# Inverter.net
KiCad netlist of a schematic drawn in Altium Designer
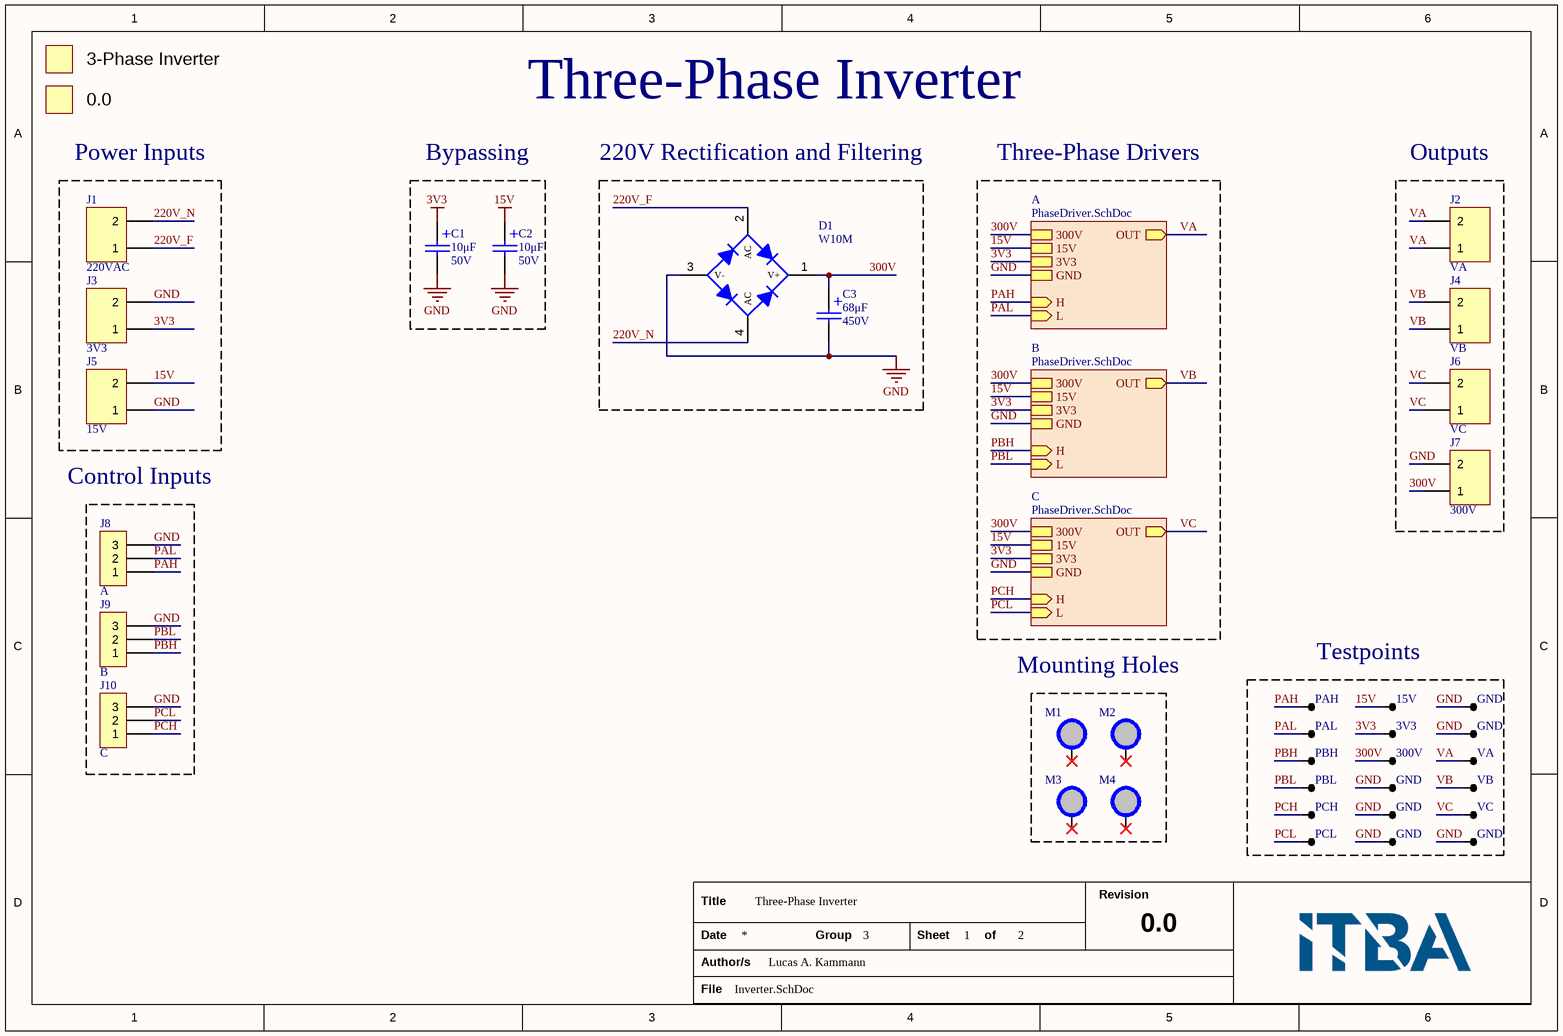
[diagram p0: Inverter.SchDoc]

(export (version "E")
  (design (tool "Eeschema 10.0.6"))
  (components
    (comp (ref "B1")
      (value "Board Name")
      (footprint "MISC_BOARD")
      (fields (field (name "NAME") "3-Phase Inverter"))
      (libsource (lib "Inverter") (part "MISC_BOARD"))
    )
    (comp (ref "C1")
      (value "10μF")
      (footprint "CAP100RP")
      (description "CAPACITOR POLARIZADO")
      (fields (field (name "VOLTAGE RATING") "50V") (field (name "Comment") "CAPPOL"))
      (libsource (lib "Inverter") (part "CAPACITOR POLARIZADO"))
    )
    (comp (ref "C2")
      (value "10μF")
      (footprint "CAP100RP")
      (description "CAPACITOR POLARIZADO")
      (fields (field (name "VOLTAGE RATING") "50V") (field (name "Comment") "CAPPOL"))
      (libsource (lib "Inverter") (part "CAPACITOR POLARIZADO"))
    )
    (comp (ref "C3")
      (value "68μF")
      (footprint "CAP_8mm")
      (description "CAPACITOR POLARIZADO")
      (fields (field (name "VOLTAGE RATING") "450V") (field (name "Comment") "CAPPOL"))
      (libsource (lib "Inverter") (part "CAPACITOR POLARIZADO"))
    )
    (comp (ref "D1") (value "W10M") (footprint "PUENTE - W10M") (libsource (lib "Inverter") (part "W10M")))
    (comp (ref "J1")
      (value "220VAC")
      (footprint "BORNERA2")
      (description "BORNERA 2 POLOS")
      (libsource (lib "Inverter") (part "BORNERA 2"))
    )
    (comp (ref "J2")
      (value "VA")
      (footprint "BORNERA2")
      (description "BORNERA 2 POLOS")
      (libsource (lib "") (part "BORNERA 2_1"))
    )
    (comp (ref "J3")
      (value "3V3")
      (footprint "BORNERA2")
      (description "BORNERA 2 POLOS")
      (libsource (lib "Inverter") (part "BORNERA 2"))
    )
    (comp (ref "J4")
      (value "VB")
      (footprint "BORNERA2")
      (description "BORNERA 2 POLOS")
      (libsource (lib "") (part "BORNERA 2_1"))
    )
    (comp (ref "J5")
      (value "15V")
      (footprint "BORNERA2")
      (description "BORNERA 2 POLOS")
      (libsource (lib "Inverter") (part "BORNERA 2"))
    )
    (comp (ref "J6")
      (value "VC")
      (footprint "BORNERA2")
      (description "BORNERA 2 POLOS")
      (libsource (lib "") (part "BORNERA 2_1"))
    )
    (comp (ref "J7")
      (value "300V")
      (footprint "BORNERA2")
      (description "BORNERA 2 POLOS")
      (libsource (lib "") (part "BORNERA 2_1"))
    )
    (comp (ref "J8") (value "A") (footprint "SIP3") (libsource (lib "*") (part "CON3")))
    (comp (ref "J9") (value "B") (footprint "SIP3") (libsource (lib "*") (part "CON3")))
    (comp (ref "J10") (value "C") (footprint "SIP3") (libsource (lib "*") (part "CON3")))
    (comp (ref "M1")
      (value "Mounting Hole")
      (footprint "MISC_MOUNTING_HOLE_M3")
      (description "MOUNTING HOLE M2.5")
      (libsource (lib "Inverter") (part "MISC_MOUNTING_HOLE_M3"))
    )
    (comp (ref "M2")
      (value "Mounting Hole")
      (footprint "MISC_MOUNTING_HOLE_M3")
      (description "MOUNTING HOLE M2.5")
      (libsource (lib "Inverter") (part "MISC_MOUNTING_HOLE_M3"))
    )
    (comp (ref "M3")
      (value "Mounting Hole")
      (footprint "MISC_MOUNTING_HOLE_M3")
      (description "MOUNTING HOLE M2.5")
      (libsource (lib "Inverter") (part "MISC_MOUNTING_HOLE_M3"))
    )
    (comp (ref "M4")
      (value "Mounting Hole")
      (footprint "MISC_MOUNTING_HOLE_M3")
      (description "MOUNTING HOLE M2.5")
      (libsource (lib "Inverter") (part "MISC_MOUNTING_HOLE_M3"))
    )
    (comp (ref "TP1")
      (value "PAH")
      (footprint "TPTH")
      (description "TESTPOINT")
      (libsource (lib "Inverter") (part "TP"))
    )
    (comp (ref "TP2")
      (value "15V")
      (footprint "TPTH")
      (description "TESTPOINT")
      (libsource (lib "Inverter") (part "TP"))
    )
    (comp (ref "TP3")
      (value "GND")
      (footprint "TPTH")
      (description "TESTPOINT")
      (libsource (lib "Inverter") (part "TP"))
    )
    (comp (ref "TP4")
      (value "PAL")
      (footprint "TPTH")
      (description "TESTPOINT")
      (libsource (lib "Inverter") (part "TP"))
    )
    (comp (ref "TP5")
      (value "3V3")
      (footprint "TPTH")
      (description "TESTPOINT")
      (libsource (lib "Inverter") (part "TP"))
    )
    (comp (ref "TP6")
      (value "GND")
      (footprint "TPTH")
      (description "TESTPOINT")
      (libsource (lib "Inverter") (part "TP"))
    )
    (comp (ref "TP7")
      (value "PBH")
      (footprint "TPTH")
      (description "TESTPOINT")
      (libsource (lib "Inverter") (part "TP"))
    )
    (comp (ref "TP8")
      (value "300V")
      (footprint "TPTH")
      (description "TESTPOINT")
      (libsource (lib "Inverter") (part "TP"))
    )
    (comp (ref "TP9")
      (value "VA")
      (footprint "TPTH")
      (description "TESTPOINT")
      (libsource (lib "Inverter") (part "TP"))
    )
    (comp (ref "TP10")
      (value "PBL")
      (footprint "TPTH")
      (description "TESTPOINT")
      (libsource (lib "Inverter") (part "TP"))
    )
    (comp (ref "TP11")
      (value "GND")
      (footprint "TPTH")
      (description "TESTPOINT")
      (libsource (lib "Inverter") (part "TP"))
    )
    (comp (ref "TP12")
      (value "VB")
      (footprint "TPTH")
      (description "TESTPOINT")
      (libsource (lib "Inverter") (part "TP"))
    )
    (comp (ref "TP13")
      (value "PCH")
      (footprint "TPTH")
      (description "TESTPOINT")
      (libsource (lib "Inverter") (part "TP"))
    )
    (comp (ref "TP14")
      (value "GND")
      (footprint "TPTH")
      (description "TESTPOINT")
      (libsource (lib "Inverter") (part "TP"))
    )
    (comp (ref "TP15")
      (value "VC")
      (footprint "TPTH")
      (description "TESTPOINT")
      (libsource (lib "Inverter") (part "TP"))
    )
    (comp (ref "TP16")
      (value "PCL")
      (footprint "TPTH")
      (description "TESTPOINT")
      (libsource (lib "Inverter") (part "TP"))
    )
    (comp (ref "TP17")
      (value "GND")
      (footprint "TPTH")
      (description "TESTPOINT")
      (libsource (lib "Inverter") (part "TP"))
    )
    (comp (ref "TP18")
      (value "GND")
      (footprint "TPTH")
      (description "TESTPOINT")
      (libsource (lib "Inverter") (part "TP"))
    )
    (comp (ref "V1")
      (value "PCB Version")
      (footprint "MISC_VERSION")
      (fields (field (name "VERSION") "0.0"))
      (libsource (lib "Inverter") (part "MISC_VERSION"))
    )
  )
  (nets
    (net (code "1") (name "/220V_F") (class "Default")
      (node (ref "D1") (pin "2") (pinfunction "AC_2") (pintype "passive"))
      (node (ref "J1") (pin "1") (pinfunction "1_1") (pintype "passive"))
    )
    (net (code "2") (name "/220V_N") (class "Default")
      (node (ref "D1") (pin "4") (pinfunction "AC_4") (pintype "passive"))
      (node (ref "J1") (pin "2") (pinfunction "2_2") (pintype "passive"))
    )
    (net (code "3") (name "/300V") (class "Default")
      (node (ref "C3") (pin "1") (pinfunction "1_1") (pintype "passive"))
      (node (ref "D1") (pin "1") (pinfunction "V+_1") (pintype "passive"))
      (node (ref "J7") (pin "1") (pinfunction "1_1") (pintype "passive"))
      (node (ref "TP8") (pin "1") (pinfunction "1_1") (pintype "passive"))
    )
    (net (code "4") (name "/PAH") (class "Default")
      (node (ref "J8") (pin "1") (pinfunction "1_1") (pintype "passive"))
      (node (ref "TP1") (pin "1") (pinfunction "1_1") (pintype "passive"))
    )
    (net (code "5") (name "/PAL") (class "Default")
      (node (ref "J8") (pin "2") (pinfunction "2_2") (pintype "passive"))
      (node (ref "TP4") (pin "1") (pinfunction "1_1") (pintype "passive"))
    )
    (net (code "6") (name "/PBH") (class "Default")
      (node (ref "J9") (pin "1") (pinfunction "1_1") (pintype "passive"))
      (node (ref "TP7") (pin "1") (pinfunction "1_1") (pintype "passive"))
    )
    (net (code "7") (name "/PBL") (class "Default")
      (node (ref "J9") (pin "2") (pinfunction "2_2") (pintype "passive"))
      (node (ref "TP10") (pin "1") (pinfunction "1_1") (pintype "passive"))
    )
    (net (code "8") (name "/PCH") (class "Default")
      (node (ref "J10") (pin "1") (pinfunction "1_1") (pintype "passive"))
      (node (ref "TP13") (pin "1") (pinfunction "1_1") (pintype "passive"))
    )
    (net (code "9") (name "/PCL") (class "Default")
      (node (ref "J10") (pin "2") (pinfunction "2_2") (pintype "passive"))
      (node (ref "TP16") (pin "1") (pinfunction "1_1") (pintype "passive"))
    )
    (net (code "10") (name "/VA") (class "Default")
      (node (ref "J2") (pin "1") (pinfunction "1_1") (pintype "passive"))
      (node (ref "J2") (pin "2") (pinfunction "2_2") (pintype "passive"))
      (node (ref "TP9") (pin "1") (pinfunction "1_1") (pintype "passive"))
    )
    (net (code "11") (name "/VB") (class "Default")
      (node (ref "J4") (pin "1") (pinfunction "1_1") (pintype "passive"))
      (node (ref "J4") (pin "2") (pinfunction "2_2") (pintype "passive"))
      (node (ref "TP12") (pin "1") (pinfunction "1_1") (pintype "passive"))
    )
    (net (code "12") (name "/VC") (class "Default")
      (node (ref "J6") (pin "1") (pinfunction "1_1") (pintype "passive"))
      (node (ref "J6") (pin "2") (pinfunction "2_2") (pintype "passive"))
      (node (ref "TP15") (pin "1") (pinfunction "1_1") (pintype "passive"))
    )
    (net (code "13") (name "3V3") (class "Default")
      (node (ref "C1") (pin "1") (pinfunction "1_1") (pintype "passive"))
      (node (ref "J3") (pin "1") (pinfunction "1_1") (pintype "passive"))
      (node (ref "TP5") (pin "1") (pinfunction "1_1") (pintype "passive"))
    )
    (net (code "14") (name "15V") (class "Default")
      (node (ref "C2") (pin "1") (pinfunction "1_1") (pintype "passive"))
      (node (ref "J5") (pin "2") (pinfunction "2_2") (pintype "passive"))
      (node (ref "TP2") (pin "1") (pinfunction "1_1") (pintype "passive"))
    )
    (net (code "15") (name "GND") (class "Default")
      (node (ref "C1") (pin "2") (pinfunction "2_2") (pintype "passive"))
      (node (ref "C2") (pin "2") (pinfunction "2_2") (pintype "passive"))
      (node (ref "C3") (pin "2") (pinfunction "2_2") (pintype "passive"))
      (node (ref "D1") (pin "3") (pinfunction "V-_3") (pintype "passive"))
      (node (ref "J10") (pin "3") (pinfunction "3_3") (pintype "passive"))
      (node (ref "J3") (pin "2") (pinfunction "2_2") (pintype "passive"))
      (node (ref "J5") (pin "1") (pinfunction "1_1") (pintype "passive"))
      (node (ref "J7") (pin "2") (pinfunction "2_2") (pintype "passive"))
      (node (ref "J8") (pin "3") (pinfunction "3_3") (pintype "passive"))
      (node (ref "J9") (pin "3") (pinfunction "3_3") (pintype "passive"))
      (node (ref "TP11") (pin "1") (pinfunction "1_1") (pintype "passive"))
      (node (ref "TP14") (pin "1") (pinfunction "1_1") (pintype "passive"))
      (node (ref "TP17") (pin "1") (pinfunction "1_1") (pintype "passive"))
      (node (ref "TP18") (pin "1") (pinfunction "1_1") (pintype "passive"))
      (node (ref "TP3") (pin "1") (pinfunction "1_1") (pintype "passive"))
      (node (ref "TP6") (pin "1") (pinfunction "1_1") (pintype "passive"))
    )
    (net (code "16") (name "unconnected-(M1-Pad1)") (class "Default")
      (node (ref "M1") (pin "1") (pinfunction "1_1") (pintype "passive+no_connect"))
    )
    (net (code "17") (name "unconnected-(M2-Pad1)") (class "Default")
      (node (ref "M2") (pin "1") (pinfunction "1_1") (pintype "passive+no_connect"))
    )
    (net (code "18") (name "unconnected-(M3-Pad1)") (class "Default")
      (node (ref "M3") (pin "1") (pinfunction "1_1") (pintype "passive+no_connect"))
    )
    (net (code "19") (name "unconnected-(M4-Pad1)") (class "Default")
      (node (ref "M4") (pin "1") (pinfunction "1_1") (pintype "passive+no_connect"))
    )
  )
)
